# WiFiKernel.net
KiCad netlist of a schematic drawn in Altium Designer
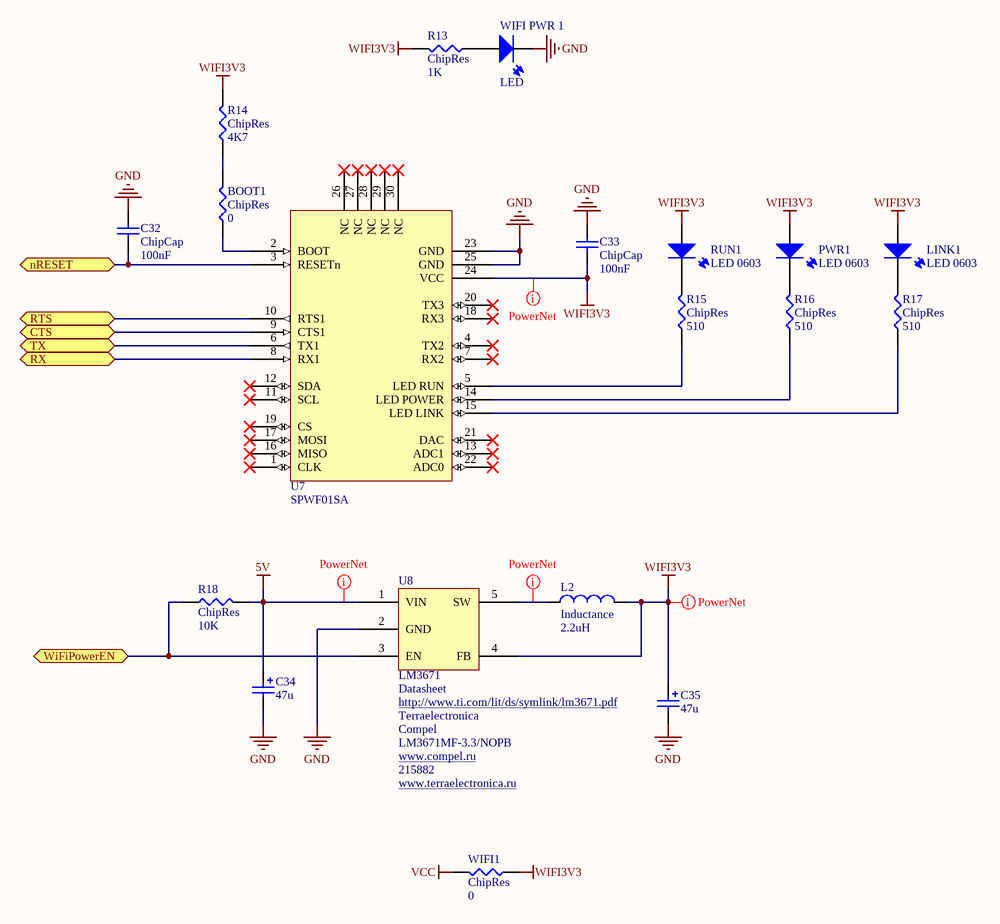
[diagram p0: WiFiKernel.SchDoc]

(export (version "E")
  (design (tool "Eeschema 10.0.6"))
  (components
    (comp (ref "BOOT1")
      (value "ChipRes")
      (footprint "RES0805")
      (description "Chip resistor")
      (fields (field (name "ALTIUM_VALUE") "0"))
      (libsource (lib "Common Devices") (part "ChipRes"))
    )
    (comp (ref "C32")
      (value "ChipCap")
      (footprint "CAP0805")
      (description "Capacitor")
      (fields (field (name "ALTIUM_VALUE") "100nF") (field (name "PUBLISHER") "Altium Limited"))
      (libsource (lib "Common Devices") (part "ChipCap"))
    )
    (comp (ref "C33")
      (value "ChipCap")
      (footprint "CAP0805")
      (description "Capacitor")
      (fields (field (name "ALTIUM_VALUE") "100nF") (field (name "PUBLISHER") "Altium Limited"))
      (libsource (lib "Common Devices") (part "ChipCap"))
    )
    (comp (ref "C34")
      (value "47u")
      (footprint "CAPC7343")
      (description "Polarized Capacitor (Radial)")
      (fields (field (name "Comment") "Cap Pol SMD"))
      (libsource (lib "Common Devices") (part "Cap Pol Chip"))
    )
    (comp (ref "C35")
      (value "47u")
      (footprint "CAPC7343")
      (description "Polarized Capacitor (Radial)")
      (fields (field (name "Comment") "Cap Pol SMD"))
      (libsource (lib "Common Devices") (part "Cap Pol Chip"))
    )
    (comp (ref "L2")
      (value "Inductance")
      (footprint "CDRH2D14")
      (fields (field (name "ALTIUM_VALUE") "2.2uH"))
      (libsource (lib "Common Devices") (part "ChipInductance"))
    )
    (comp (ref "LINK1") (value "LED 0603") (footprint "LED 0603") (libsource (lib "LEDs") (part "LED0603")))
    (comp (ref "PWR1") (value "LED 0603") (footprint "LED 0603") (libsource (lib "LEDs") (part "LED0603")))
    (comp (ref "R13")
      (value "ChipRes")
      (footprint "RES0805")
      (description "Chip resistor")
      (fields (field (name "ALTIUM_VALUE") "1K"))
      (libsource (lib "Common Devices") (part "ChipRes"))
    )
    (comp (ref "R14")
      (value "ChipRes")
      (footprint "RES0805")
      (description "Chip resistor")
      (fields (field (name "ALTIUM_VALUE") "4K7"))
      (libsource (lib "Common Devices") (part "ChipRes"))
    )
    (comp (ref "R15")
      (value "ChipRes")
      (footprint "RES0805")
      (description "Chip resistor")
      (fields (field (name "ALTIUM_VALUE") "510"))
      (libsource (lib "Common Devices") (part "ChipRes"))
    )
    (comp (ref "R16")
      (value "ChipRes")
      (footprint "RES0805")
      (description "Chip resistor")
      (fields (field (name "ALTIUM_VALUE") "510"))
      (libsource (lib "Common Devices") (part "ChipRes"))
    )
    (comp (ref "R17")
      (value "ChipRes")
      (footprint "RES0805")
      (description "Chip resistor")
      (fields (field (name "ALTIUM_VALUE") "510"))
      (libsource (lib "Common Devices") (part "ChipRes"))
    )
    (comp (ref "R18")
      (value "ChipRes")
      (footprint "RES0805")
      (description "Chip resistor")
      (fields (field (name "ALTIUM_VALUE") "10K"))
      (libsource (lib "Common Devices") (part "ChipRes"))
    )
    (comp (ref "RUN1") (value "LED 0603") (footprint "LED 0603") (libsource (lib "LEDs") (part "LED0603")))
    (comp (ref "U7")
      (value "SPWF01SA")
      (footprint "SPWF01SA")
      (description "Serial-to-Wi-Fi b/g/n intelligent module")
      (libsource (lib "WiFiModules") (part "SPWF01"))
    )
    (comp (ref "U8")
      (value "LM3671")
      (footprint "SOT23-5")
      (description "600-mA Step-Down DC-DC Converter")
      (fields
        (field (name "COMPONENTLINK1DESCRIPTION") "Datasheet")
        (field (name "COMPONENTLINK1URL") "http://www.ti.com/lit/ds/symlink/lm3671.pdf")
        (field (name "SUPPLIER 1") "Terraelectronica")
        (field (name "SUPPLIER 2") "Compel")
        (field (name "SUPPLIER PART NUMBER 2") "LM3671MF-3.3/NOPB")
        (field (name "SUPPLIER URL 2") "www.compel.ru")
        (field (name "SUPPLIER PART NUMBER 1") "215882")
        (field (name "SUPPLIER URL 1") "www.terraelectronica.ru")
      )
      (libsource (lib "TI DC-DC Convertors") (part "LM3671MF"))
    )
    (comp (ref "WIFI PWR 1") (value "LED") (footprint "PLCC-2") (libsource (lib "LEDs") (part "LED0603")))
    (comp (ref "WIFI1")
      (value "ChipRes")
      (footprint "RES0805")
      (description "Chip resistor")
      (fields (field (name "ALTIUM_VALUE") "0"))
      (libsource (lib "Common Devices") (part "ChipRes"))
    )
  )
  (nets
    (net (code "1") (name "/CTS") (class "Default")
      (node (ref "U7") (pin "9") (pinfunction "CTS1_9") (pintype "input"))
    )
    (net (code "2") (name "/RTS") (class "Default")
      (node (ref "U7") (pin "10") (pinfunction "RTS1_10") (pintype "output"))
    )
    (net (code "3") (name "/RX") (class "Default")
      (node (ref "U7") (pin "8") (pinfunction "RX1_8") (pintype "input"))
    )
    (net (code "4") (name "/TX") (class "Default")
      (node (ref "U7") (pin "6") (pinfunction "TX1_6") (pintype "output"))
    )
    (net (code "5") (name "/WiFiPowerEN") (class "Default")
      (node (ref "R18") (pin "1") (pintype "passive"))
      (node (ref "U8") (pin "3") (pinfunction "EN_3") (pintype "passive"))
    )
    (net (code "6") (name "/nRESET") (class "Default")
      (node (ref "C32") (pin "2") (pinfunction "2_2") (pintype "passive"))
      (node (ref "U7") (pin "3") (pinfunction "RESETn_3") (pintype "input"))
    )
    (net (code "7") (name "5V") (class "Default")
      (node (ref "C34") (pin "1") (pinfunction "1_1") (pintype "passive"))
      (node (ref "R18") (pin "2") (pintype "passive"))
      (node (ref "U8") (pin "1") (pinfunction "VIN_1") (pintype "passive"))
    )
    (net (code "8") (name "GND") (class "Default")
      (node (ref "C32") (pin "1") (pinfunction "1_1") (pintype "passive"))
      (node (ref "C33") (pin "1") (pinfunction "1_1") (pintype "passive"))
      (node (ref "C34") (pin "2") (pinfunction "2_2") (pintype "passive"))
      (node (ref "C35") (pin "2") (pinfunction "2_2") (pintype "passive"))
      (node (ref "U7") (pin "23") (pinfunction "GND_23") (pintype "passive"))
      (node (ref "U7") (pin "25") (pinfunction "GND_25") (pintype "passive"))
      (node (ref "U8") (pin "2") (pinfunction "GND_2") (pintype "passive"))
      (node (ref "WIFI PWR 1") (pin "1") (pinfunction "1_1") (pintype "passive"))
    )
    (net (code "9") (name "Net-(BOOT1-Pad1)") (class "Default")
      (node (ref "BOOT1") (pin "1") (pintype "passive"))
      (node (ref "R14") (pin "2") (pintype "passive"))
    )
    (net (code "10") (name "Net-(LINK1-Pad1)") (class "Default")
      (node (ref "LINK1") (pin "1") (pinfunction "1_1") (pintype "passive"))
      (node (ref "R17") (pin "1") (pintype "passive"))
    )
    (net (code "11") (name "Net-(PWR1-Pad1)") (class "Default")
      (node (ref "PWR1") (pin "1") (pinfunction "1_1") (pintype "passive"))
      (node (ref "R16") (pin "1") (pintype "passive"))
    )
    (net (code "12") (name "Net-(R13-Pad1)") (class "Default")
      (node (ref "R13") (pin "1") (pintype "passive"))
      (node (ref "WIFI PWR 1") (pin "2") (pinfunction "2_2") (pintype "passive"))
    )
    (net (code "13") (name "Net-(R15-Pad1)") (class "Default")
      (node (ref "R15") (pin "1") (pintype "passive"))
      (node (ref "RUN1") (pin "1") (pinfunction "1_1") (pintype "passive"))
    )
    (net (code "14") (name "Net-(U7-BOOT)") (class "Default")
      (node (ref "BOOT1") (pin "2") (pintype "passive"))
      (node (ref "U7") (pin "2") (pinfunction "BOOT_2") (pintype "input"))
    )
    (net (code "15") (name "Net-(U7-LED_LINK)") (class "Default")
      (node (ref "R17") (pin "2") (pintype "passive"))
      (node (ref "U7") (pin "15") (pinfunction "LED_LINK_15") (pintype "bidirectional"))
    )
    (net (code "16") (name "Net-(U7-LED_POWER)") (class "Default")
      (node (ref "R16") (pin "2") (pintype "passive"))
      (node (ref "U7") (pin "14") (pinfunction "LED_POWER_14") (pintype "bidirectional"))
    )
    (net (code "17") (name "Net-(U7-LED_RUN)") (class "Default")
      (node (ref "R15") (pin "2") (pintype "passive"))
      (node (ref "U7") (pin "5") (pinfunction "LED_RUN_5") (pintype "bidirectional"))
    )
    (net (code "18") (name "Net-(U8-SW)") (class "Default")
      (node (ref "L2") (pin "2") (pintype "passive"))
      (node (ref "U8") (pin "5") (pinfunction "SW_5") (pintype "passive"))
    )
    (net (code "19") (name "VCC") (class "Default") (node (ref "WIFI1") (pin "2") (pintype "passive")))
    (net (code "20") (name "WIFI3V3") (class "Default")
      (node (ref "C33") (pin "2") (pinfunction "2_2") (pintype "passive"))
      (node (ref "C35") (pin "1") (pinfunction "1_1") (pintype "passive"))
      (node (ref "L2") (pin "1") (pintype "passive"))
      (node (ref "LINK1") (pin "2") (pinfunction "2_2") (pintype "passive"))
      (node (ref "PWR1") (pin "2") (pinfunction "2_2") (pintype "passive"))
      (node (ref "R13") (pin "2") (pintype "passive"))
      (node (ref "R14") (pin "1") (pintype "passive"))
      (node (ref "RUN1") (pin "2") (pinfunction "2_2") (pintype "passive"))
      (node (ref "U7") (pin "24") (pinfunction "VCC_24") (pintype "power_in"))
      (node (ref "U8") (pin "4") (pinfunction "FB_4") (pintype "passive"))
      (node (ref "WIFI1") (pin "1") (pintype "passive"))
    )
    (net (code "21") (name "unconnected-(U7-ADC0-Pad22)") (class "Default")
      (node (ref "U7") (pin "22") (pinfunction "ADC0_22") (pintype "bidirectional+no_connect"))
    )
    (net (code "22") (name "unconnected-(U7-ADC1-Pad13)") (class "Default")
      (node (ref "U7") (pin "13") (pinfunction "ADC1_13") (pintype "bidirectional+no_connect"))
    )
    (net (code "23") (name "unconnected-(U7-CLK-Pad1)") (class "Default")
      (node (ref "U7") (pin "1") (pinfunction "CLK_1") (pintype "bidirectional+no_connect"))
    )
    (net (code "24") (name "unconnected-(U7-CS-Pad19)") (class "Default")
      (node (ref "U7") (pin "19") (pinfunction "CS_19") (pintype "bidirectional+no_connect"))
    )
    (net (code "25") (name "unconnected-(U7-DAC-Pad21)") (class "Default")
      (node (ref "U7") (pin "21") (pinfunction "DAC_21") (pintype "bidirectional+no_connect"))
    )
    (net (code "26") (name "unconnected-(U7-MISO-Pad16)") (class "Default")
      (node (ref "U7") (pin "16") (pinfunction "MISO_16") (pintype "bidirectional+no_connect"))
    )
    (net (code "27") (name "unconnected-(U7-MOSI-Pad17)") (class "Default")
      (node (ref "U7") (pin "17") (pinfunction "MOSI_17") (pintype "bidirectional+no_connect"))
    )
    (net (code "28") (name "unconnected-(U7-NC-Pad26)") (class "Default")
      (node (ref "U7") (pin "26") (pinfunction "NC_26") (pintype "passive+no_connect"))
    )
    (net (code "29") (name "unconnected-(U7-NC-Pad27)") (class "Default")
      (node (ref "U7") (pin "27") (pinfunction "NC_27") (pintype "passive+no_connect"))
    )
    (net (code "30") (name "unconnected-(U7-NC-Pad28)") (class "Default")
      (node (ref "U7") (pin "28") (pinfunction "NC_28") (pintype "passive+no_connect"))
    )
    (net (code "31") (name "unconnected-(U7-NC-Pad29)") (class "Default")
      (node (ref "U7") (pin "29") (pinfunction "NC_29") (pintype "passive+no_connect"))
    )
    (net (code "32") (name "unconnected-(U7-NC-Pad30)") (class "Default")
      (node (ref "U7") (pin "30") (pinfunction "NC_30") (pintype "passive+no_connect"))
    )
    (net (code "33") (name "unconnected-(U7-RX2-Pad7)") (class "Default")
      (node (ref "U7") (pin "7") (pinfunction "RX2_7") (pintype "bidirectional+no_connect"))
    )
    (net (code "34") (name "unconnected-(U7-RX3-Pad18)") (class "Default")
      (node (ref "U7") (pin "18") (pinfunction "RX3_18") (pintype "bidirectional+no_connect"))
    )
    (net (code "35") (name "unconnected-(U7-SCL-Pad11)") (class "Default")
      (node (ref "U7") (pin "11") (pinfunction "SCL_11") (pintype "bidirectional+no_connect"))
    )
    (net (code "36") (name "unconnected-(U7-SDA-Pad12)") (class "Default")
      (node (ref "U7") (pin "12") (pinfunction "SDA_12") (pintype "bidirectional+no_connect"))
    )
    (net (code "37") (name "unconnected-(U7-TX2-Pad4)") (class "Default")
      (node (ref "U7") (pin "4") (pinfunction "TX2_4") (pintype "bidirectional+no_connect"))
    )
    (net (code "38") (name "unconnected-(U7-TX3-Pad20)") (class "Default")
      (node (ref "U7") (pin "20") (pinfunction "TX3_20") (pintype "bidirectional+no_connect"))
    )
  )
)
